# Tacho_SeedBauteile.net
KiCad netlist of a schematic drawn in EAGLE
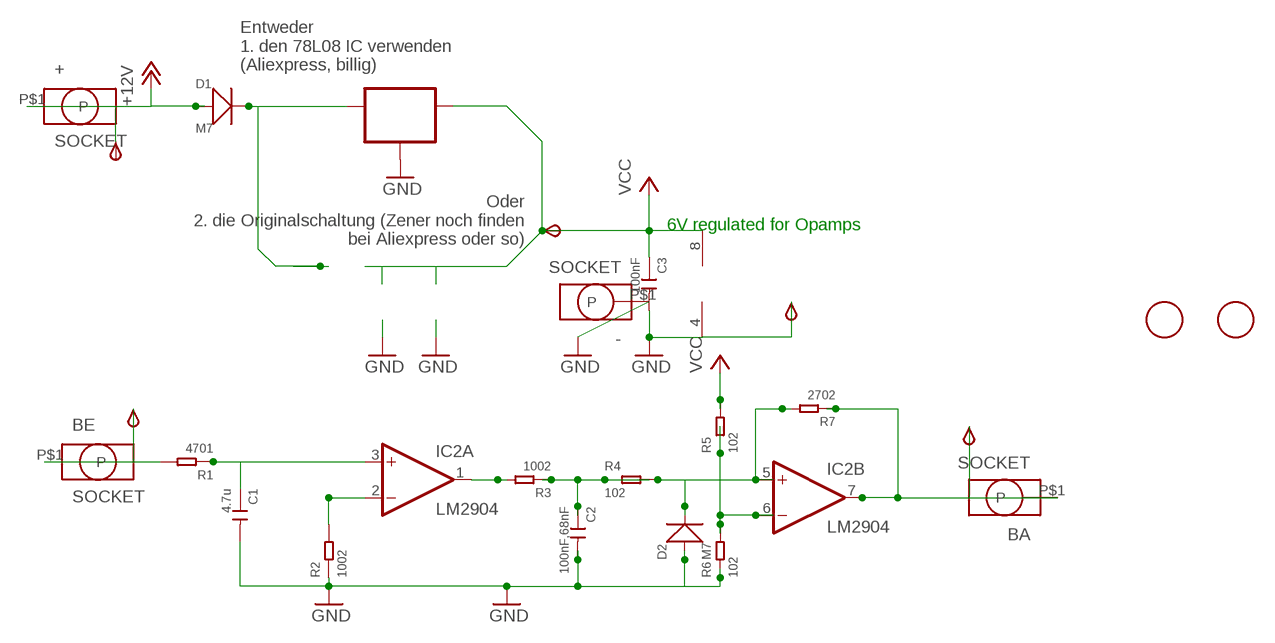
[diagram p0: schematic, sheet 1]

(export (version "E")
  (design (tool "Eeschema 10.0.6"))
  (components
    (comp (ref "+")
      (value "SOCKET")
      (footprint "eagle-import:ID2.5MM")
      (libsource (lib "eagle-import") (part "SOCKET"))
    )
    (comp (ref "+12V")
      (value "TPSB2.0")
      (footprint "eagle-import:B2.0")
      (libsource (lib "eagle-import") (part "TPSB2.0"))
    )
    (comp (ref "-")
      (value "SOCKET")
      (footprint "eagle-import:ID2.5MM")
      (libsource (lib "eagle-import") (part "SOCKET"))
    )
    (comp (ref "6V")
      (value "TPSB2.0")
      (footprint "eagle-import:B2.0")
      (libsource (lib "eagle-import") (part "TPSB2.0"))
    )
    (comp (ref "AUS")
      (value "TPSB2.0")
      (footprint "eagle-import:B2.0")
      (libsource (lib "eagle-import") (part "TPSB2.0"))
    )
    (comp (ref "BA")
      (value "SOCKET")
      (footprint "eagle-import:ID2.5MM")
      (libsource (lib "eagle-import") (part "SOCKET"))
    )
    (comp (ref "BE")
      (value "SOCKET")
      (footprint "eagle-import:ID2.5MM")
      (libsource (lib "eagle-import") (part "SOCKET"))
    )
    (comp (ref "C1")
      (value "4.7u")
      (footprint "eagle-import:C0805")
      (fields (field (name "MPN") "CC0805KKX5R8BB475"))
      (libsource (lib "eagle-import") (part "CERAMIC-4.7UF-25V-10%-X5R(0805)"))
    )
    (comp (ref "C2")
      (value "100nF,68nF")
      (footprint "eagle-import:C0805")
      (fields (field (name "MPN") "CC0805KRX7R9BB104"))
      (libsource (lib "eagle-import") (part "CERAMIC-100NF-50V-10%-X7R(0805)"))
    )
    (comp (ref "C3")
      (value "100nF")
      (footprint "eagle-import:C0805")
      (fields (field (name "MPN") "CC0805KRX7R9BB104"))
      (libsource (lib "eagle-import") (part "CERAMIC-100NF-50V-10%-X7R(0805)"))
    )
    (comp (ref "D1")
      (value "M7")
      (footprint "eagle-import:DO-214AC")
      (fields (field (name "MPN") "1N4007"))
      (libsource (lib "eagle-import") (part "DIODE-GEN-PURPOSE-1KV-1A(DO-214AC)"))
    )
    (comp (ref "D2")
      (value "M7")
      (footprint "eagle-import:DO-214AC")
      (fields (field (name "MPN") "1N4007"))
      (libsource (lib "eagle-import") (part "DIODE-GEN-PURPOSE-1KV-1A(DO-214AC)"))
    )
    (comp (ref "EIN")
      (value "TPSB2.0")
      (footprint "eagle-import:B2.0")
      (libsource (lib "eagle-import") (part "TPSB2.0"))
    )
    (comp (ref "FID1")
      (value "FIDUCIAL")
      (footprint "eagle-import:FIDUCIAL_1MM")
      (libsource (lib "eagle-import") (part "FIDUCIAL"))
    )
    (comp (ref "FID2")
      (value "FIDUCIAL")
      (footprint "eagle-import:FIDUCIAL_1MM")
      (libsource (lib "eagle-import") (part "FIDUCIAL"))
    )
    (comp (ref "GND")
      (value "TPSB2.0")
      (footprint "eagle-import:B2.0")
      (libsource (lib "eagle-import") (part "TPSB2.0"))
    )
    (comp (ref "IC1")
      (value "5V/6V oder 8V Regler")
      (footprint "eagle-import:SOT89_ROUND")
      (libsource (lib "eagle-import") (part "78LXXSOT89_ROUND"))
    )
    (comp (ref "IC2")
      (value "LM2904")
      (footprint "eagle-import:SO08")
      (libsource (lib "eagle-import") (part "LM358D"))
    )
    (comp (ref "R1")
      (value "4701")
      (footprint "eagle-import:R0805")
      (fields (field (name "MPN") "RC0805JR-074K7L"))
      (libsource (lib "eagle-import") (part "SMD-RES-4.7K-5%-1/8W(0805)"))
    )
    (comp (ref "R2")
      (value "1002")
      (footprint "eagle-import:R0805")
      (fields (field (name "MPN") "RC0805FR-0710KL"))
      (libsource (lib "eagle-import") (part "SMD-RES-10K-1%-1/8W(0805)"))
    )
    (comp (ref "R3")
      (value "1002")
      (footprint "eagle-import:R0805")
      (fields (field (name "MPN") "RC0805FR-0710KL"))
      (libsource (lib "eagle-import") (part "SMD-RES-10K-1%-1/8W(0805)"))
    )
    (comp (ref "R4")
      (value "102")
      (footprint "eagle-import:R0805")
      (fields (field (name "MPN") "RC0805JR-071KL"))
      (libsource (lib "eagle-import") (part "SMD-RES-1K-5%-1/8W(0805)"))
    )
    (comp (ref "R5")
      (value "102")
      (footprint "eagle-import:R0805")
      (fields (field (name "MPN") "RC0805JR-071KL"))
      (libsource (lib "eagle-import") (part "SMD-RES-1K-5%-1/8W(0805)"))
    )
    (comp (ref "R6")
      (value "102")
      (footprint "eagle-import:R0805")
      (fields (field (name "MPN") "RC0805JR-071KL"))
      (libsource (lib "eagle-import") (part "SMD-RES-1K-5%-1/8W(0805)"))
    )
    (comp (ref "R7")
      (value "2702")
      (footprint "eagle-import:R0805")
      (fields (field (name "MPN") "RC0805JR-074K7L"))
      (libsource (lib "eagle-import") (part "SMD-RES-4.7K-5%-1/8W(0805)"))
    )
  )
  (nets
    (net (code "1") (name "+12V") (class "Default")
      (node (ref "+") (pin "P$1") (pinfunction "P_P$1") (pintype "bidirectional"))
      (node (ref "+12V") (pin "TP") (pinfunction "PP_TP") (pintype "input"))
      (node (ref "D1") (pin "1") (pinfunction "+_1") (pintype "passive"))
    )
    (net (code "2") (name "GND") (class "Default")
      (node (ref "-") (pin "P$1") (pinfunction "P_P$1") (pintype "bidirectional"))
      (node (ref "C1") (pin "2") (pinfunction "2_2") (pintype "passive"))
      (node (ref "C2") (pin "2") (pinfunction "2_2") (pintype "passive"))
      (node (ref "C3") (pin "2") (pinfunction "2_2") (pintype "passive"))
      (node (ref "D2") (pin "1") (pinfunction "+_1") (pintype "passive"))
      (node (ref "GND") (pin "TP") (pinfunction "PP_TP") (pintype "input"))
      (node (ref "IC1") (pin "2") (pinfunction "GND_2") (pintype "input"))
      (node (ref "IC1") (pin "2@1") (pinfunction "GND_2@1") (pintype "input"))
      (node (ref "IC2") (pin "4") (pinfunction "V-_4") (pintype "power_in"))
      (node (ref "R2") (pin "1") (pinfunction "1_1") (pintype "passive"))
      (node (ref "R6") (pin "1") (pinfunction "1_1") (pintype "passive"))
    )
    (net (code "3") (name "Net-(AUS-PP)") (class "Default")
      (node (ref "AUS") (pin "TP") (pinfunction "PP_TP") (pintype "input"))
      (node (ref "BA") (pin "P$1") (pinfunction "P_P$1") (pintype "bidirectional"))
      (node (ref "IC2") (pin "7") (pinfunction "OUT_7") (pintype "output"))
      (node (ref "R7") (pin "1") (pinfunction "1_1") (pintype "passive"))
    )
    (net (code "4") (name "Net-(BE-P)") (class "Default")
      (node (ref "BE") (pin "P$1") (pinfunction "P_P$1") (pintype "bidirectional"))
      (node (ref "EIN") (pin "TP") (pinfunction "PP_TP") (pintype "input"))
      (node (ref "R1") (pin "2") (pinfunction "2_2") (pintype "passive"))
    )
    (net (code "5") (name "Net-(C2-Pad1)") (class "Default")
      (node (ref "C2") (pin "1") (pinfunction "1_1") (pintype "passive"))
      (node (ref "R3") (pin "1") (pinfunction "1_1") (pintype "passive"))
      (node (ref "R4") (pin "1") (pinfunction "1_1") (pintype "passive"))
    )
    (net (code "6") (name "Net-(D1--)") (class "Default")
      (node (ref "D1") (pin "2") (pinfunction "-_2") (pintype "passive"))
      (node (ref "IC1") (pin "3") (pinfunction "IN_3") (pintype "input"))
    )
    (net (code "7") (name "Net-(D2--)") (class "Default")
      (node (ref "D2") (pin "2") (pinfunction "-_2") (pintype "passive"))
      (node (ref "IC2") (pin "5") (pinfunction "+IN_5") (pintype "input"))
      (node (ref "R4") (pin "2") (pinfunction "2_2") (pintype "passive"))
      (node (ref "R7") (pin "2") (pinfunction "2_2") (pintype "passive"))
    )
    (net (code "8") (name "Net-(IC2A-+IN)") (class "Default")
      (node (ref "C1") (pin "1") (pinfunction "1_1") (pintype "passive"))
      (node (ref "IC2") (pin "3") (pinfunction "+IN_3") (pintype "input"))
      (node (ref "R1") (pin "1") (pinfunction "1_1") (pintype "passive"))
    )
    (net (code "9") (name "Net-(IC2A--IN)") (class "Default")
      (node (ref "IC2") (pin "2") (pinfunction "-IN_2") (pintype "input"))
      (node (ref "R2") (pin "2") (pinfunction "2_2") (pintype "passive"))
    )
    (net (code "10") (name "Net-(IC2A-OUT)") (class "Default")
      (node (ref "IC2") (pin "1") (pinfunction "OUT_1") (pintype "output"))
      (node (ref "R3") (pin "2") (pinfunction "2_2") (pintype "passive"))
    )
    (net (code "11") (name "Net-(IC2B--IN)") (class "Default")
      (node (ref "IC2") (pin "6") (pinfunction "-IN_6") (pintype "input"))
      (node (ref "R5") (pin "1") (pinfunction "1_1") (pintype "passive"))
      (node (ref "R6") (pin "2") (pinfunction "2_2") (pintype "passive"))
    )
    (net (code "12") (name "VCC") (class "Default")
      (node (ref "6V") (pin "TP") (pinfunction "PP_TP") (pintype "input"))
      (node (ref "C3") (pin "1") (pinfunction "1_1") (pintype "passive"))
      (node (ref "IC1") (pin "1") (pinfunction "OUT_1") (pintype "passive"))
      (node (ref "IC2") (pin "8") (pinfunction "V+_8") (pintype "power_in"))
      (node (ref "R5") (pin "2") (pinfunction "2_2") (pintype "passive"))
    )
  )
)
